# level_shift_panel.net
KiCad netlist of a schematic drawn in EAGLE
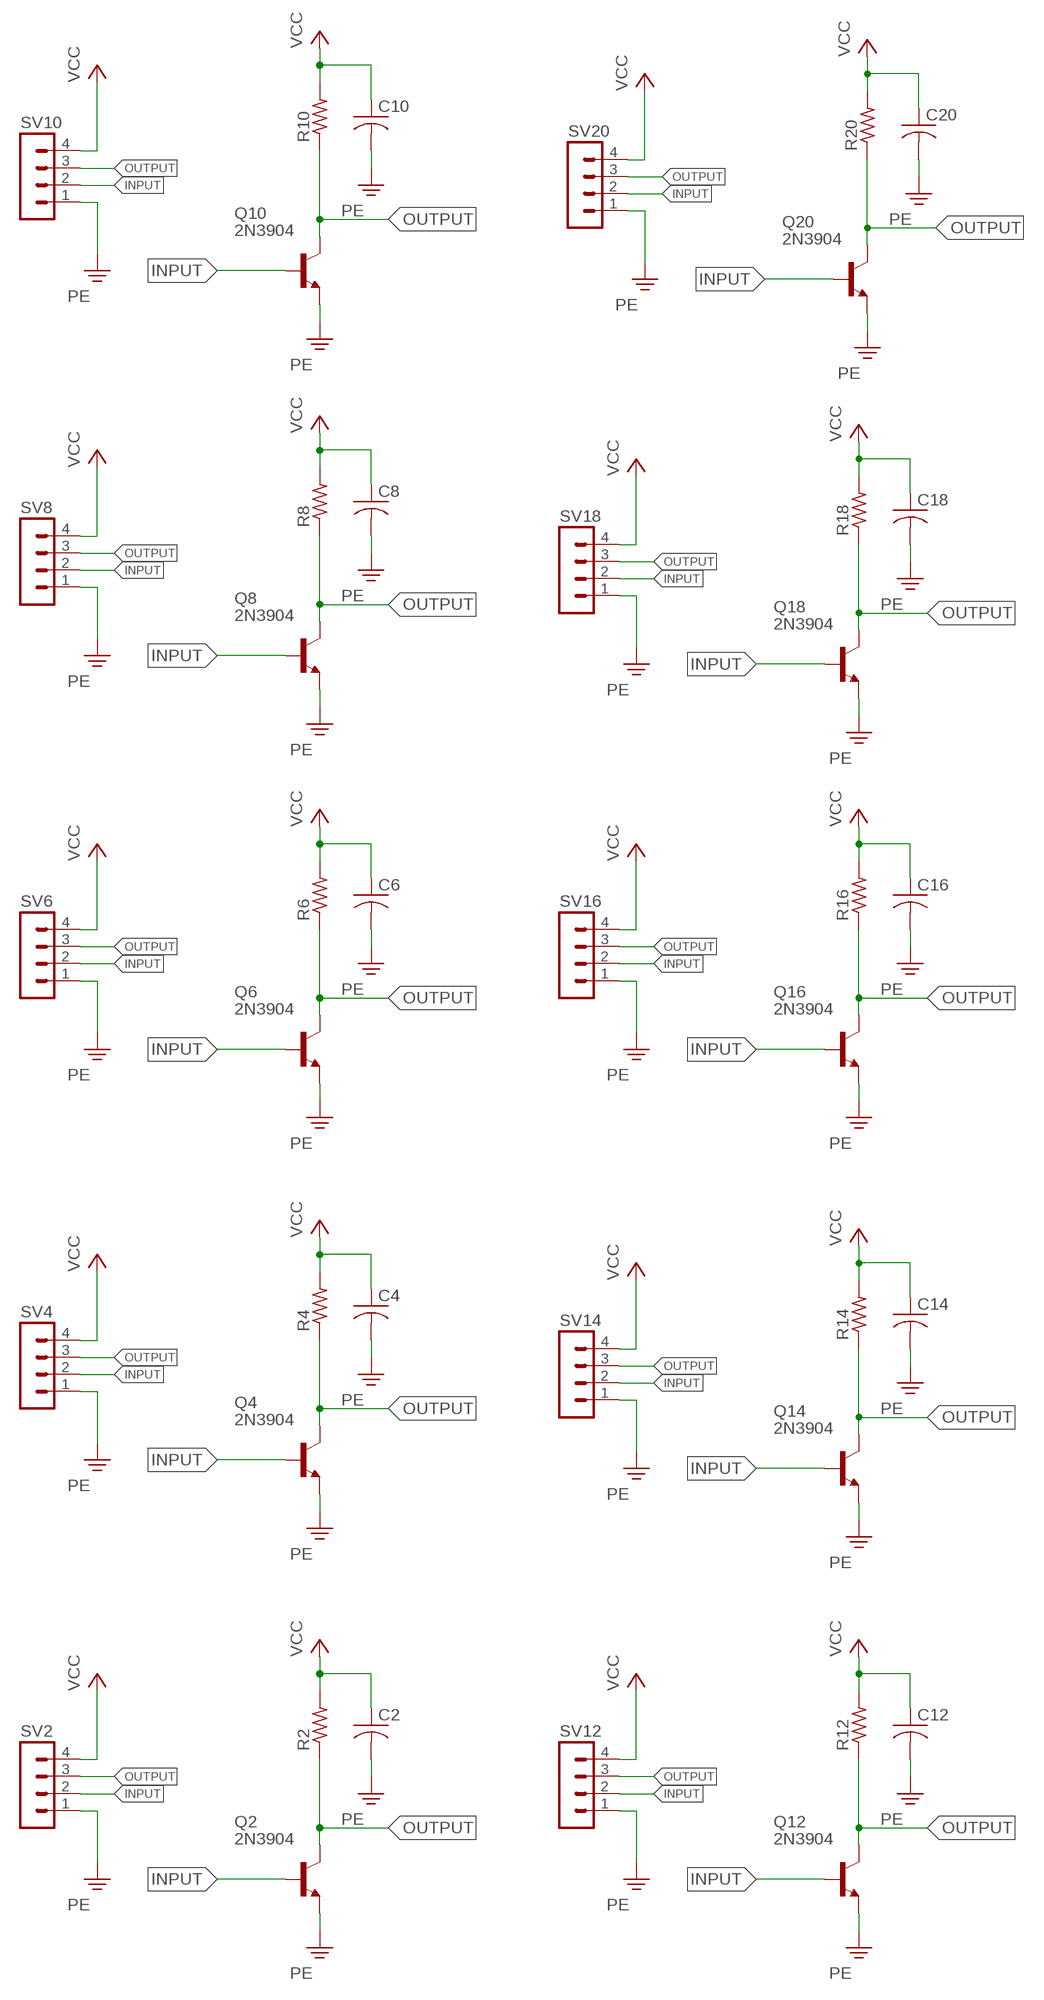
[diagram p0: schematic, sheet 1]

(export (version "E")
  (design (tool "Eeschema 10.0.6"))
  (components
    (comp (ref "C2")
      (value "C-US025-030X050")
      (footprint "eagle-import:C025-030X050")
      (libsource (lib "eagle-import") (part "C-US025-030X050"))
    )
    (comp (ref "C4")
      (value "C-US025-030X050")
      (footprint "eagle-import:C025-030X050")
      (libsource (lib "eagle-import") (part "C-US025-030X050"))
    )
    (comp (ref "C6")
      (value "C-US025-030X050")
      (footprint "eagle-import:C025-030X050")
      (libsource (lib "eagle-import") (part "C-US025-030X050"))
    )
    (comp (ref "C8")
      (value "C-US025-030X050")
      (footprint "eagle-import:C025-030X050")
      (libsource (lib "eagle-import") (part "C-US025-030X050"))
    )
    (comp (ref "C10")
      (value "C-US025-030X050")
      (footprint "eagle-import:C025-030X050")
      (libsource (lib "eagle-import") (part "C-US025-030X050"))
    )
    (comp (ref "C12")
      (value "C-US025-030X050")
      (footprint "eagle-import:C025-030X050")
      (libsource (lib "eagle-import") (part "C-US025-030X050"))
    )
    (comp (ref "C14")
      (value "C-US025-030X050")
      (footprint "eagle-import:C025-030X050")
      (libsource (lib "eagle-import") (part "C-US025-030X050"))
    )
    (comp (ref "C16")
      (value "C-US025-030X050")
      (footprint "eagle-import:C025-030X050")
      (libsource (lib "eagle-import") (part "C-US025-030X050"))
    )
    (comp (ref "C18")
      (value "C-US025-030X050")
      (footprint "eagle-import:C025-030X050")
      (libsource (lib "eagle-import") (part "C-US025-030X050"))
    )
    (comp (ref "C20")
      (value "C-US025-030X050")
      (footprint "eagle-import:C025-030X050")
      (libsource (lib "eagle-import") (part "C-US025-030X050"))
    )
    (comp (ref "Q2")
      (value "2N3904")
      (footprint "eagle-import:TO-92")
      (libsource (lib "eagle-import") (part "2N3904"))
    )
    (comp (ref "Q4")
      (value "2N3904")
      (footprint "eagle-import:TO-92")
      (libsource (lib "eagle-import") (part "2N3904"))
    )
    (comp (ref "Q6")
      (value "2N3904")
      (footprint "eagle-import:TO-92")
      (libsource (lib "eagle-import") (part "2N3904"))
    )
    (comp (ref "Q8")
      (value "2N3904")
      (footprint "eagle-import:TO-92")
      (libsource (lib "eagle-import") (part "2N3904"))
    )
    (comp (ref "Q10")
      (value "2N3904")
      (footprint "eagle-import:TO-92")
      (libsource (lib "eagle-import") (part "2N3904"))
    )
    (comp (ref "Q12")
      (value "2N3904")
      (footprint "eagle-import:TO-92")
      (libsource (lib "eagle-import") (part "2N3904"))
    )
    (comp (ref "Q14")
      (value "2N3904")
      (footprint "eagle-import:TO-92")
      (libsource (lib "eagle-import") (part "2N3904"))
    )
    (comp (ref "Q16")
      (value "2N3904")
      (footprint "eagle-import:TO-92")
      (libsource (lib "eagle-import") (part "2N3904"))
    )
    (comp (ref "Q18")
      (value "2N3904")
      (footprint "eagle-import:TO-92")
      (libsource (lib "eagle-import") (part "2N3904"))
    )
    (comp (ref "Q20")
      (value "2N3904")
      (footprint "eagle-import:TO-92")
      (libsource (lib "eagle-import") (part "2N3904"))
    )
    (comp (ref "R2")
      (value "R-US_0204/7")
      (footprint "eagle-import:0204_7")
      (libsource (lib "eagle-import") (part "R-US_0204/7"))
    )
    (comp (ref "R4")
      (value "R-US_0204/7")
      (footprint "eagle-import:0204_7")
      (libsource (lib "eagle-import") (part "R-US_0204/7"))
    )
    (comp (ref "R6")
      (value "R-US_0204/7")
      (footprint "eagle-import:0204_7")
      (libsource (lib "eagle-import") (part "R-US_0204/7"))
    )
    (comp (ref "R8")
      (value "R-US_0204/7")
      (footprint "eagle-import:0204_7")
      (libsource (lib "eagle-import") (part "R-US_0204/7"))
    )
    (comp (ref "R10")
      (value "R-US_0204/7")
      (footprint "eagle-import:0204_7")
      (libsource (lib "eagle-import") (part "R-US_0204/7"))
    )
    (comp (ref "R12")
      (value "R-US_0204/7")
      (footprint "eagle-import:0204_7")
      (libsource (lib "eagle-import") (part "R-US_0204/7"))
    )
    (comp (ref "R14")
      (value "R-US_0204/7")
      (footprint "eagle-import:0204_7")
      (libsource (lib "eagle-import") (part "R-US_0204/7"))
    )
    (comp (ref "R16")
      (value "R-US_0204/7")
      (footprint "eagle-import:0204_7")
      (libsource (lib "eagle-import") (part "R-US_0204/7"))
    )
    (comp (ref "R18")
      (value "R-US_0204/7")
      (footprint "eagle-import:0204_7")
      (libsource (lib "eagle-import") (part "R-US_0204/7"))
    )
    (comp (ref "R20")
      (value "R-US_0204/7")
      (footprint "eagle-import:0204_7")
      (libsource (lib "eagle-import") (part "R-US_0204/7"))
    )
    (comp (ref "SV2")
      (value "MA04-1")
      (footprint "eagle-import:MA04-1")
      (libsource (lib "eagle-import") (part "MA04-1"))
    )
    (comp (ref "SV4")
      (value "MA04-1")
      (footprint "eagle-import:MA04-1")
      (libsource (lib "eagle-import") (part "MA04-1"))
    )
    (comp (ref "SV6")
      (value "MA04-1")
      (footprint "eagle-import:MA04-1")
      (libsource (lib "eagle-import") (part "MA04-1"))
    )
    (comp (ref "SV8")
      (value "MA04-1")
      (footprint "eagle-import:MA04-1")
      (libsource (lib "eagle-import") (part "MA04-1"))
    )
    (comp (ref "SV10")
      (value "MA04-1")
      (footprint "eagle-import:MA04-1")
      (libsource (lib "eagle-import") (part "MA04-1"))
    )
    (comp (ref "SV12")
      (value "MA04-1")
      (footprint "eagle-import:MA04-1")
      (libsource (lib "eagle-import") (part "MA04-1"))
    )
    (comp (ref "SV14")
      (value "MA04-1")
      (footprint "eagle-import:MA04-1")
      (libsource (lib "eagle-import") (part "MA04-1"))
    )
    (comp (ref "SV16")
      (value "MA04-1")
      (footprint "eagle-import:MA04-1")
      (libsource (lib "eagle-import") (part "MA04-1"))
    )
    (comp (ref "SV18")
      (value "MA04-1")
      (footprint "eagle-import:MA04-1")
      (libsource (lib "eagle-import") (part "MA04-1"))
    )
    (comp (ref "SV20")
      (value "MA04-1")
      (footprint "eagle-import:MA04-1")
      (libsource (lib "eagle-import") (part "MA04-1"))
    )
  )
  (nets
    (net (code "1") (name "INPUT") (class "Default")
      (node (ref "Q10") (pin "B") (pinfunction "B_B") (pintype "passive"))
      (node (ref "Q12") (pin "B") (pinfunction "B_B") (pintype "passive"))
      (node (ref "Q14") (pin "B") (pinfunction "B_B") (pintype "passive"))
      (node (ref "Q16") (pin "B") (pinfunction "B_B") (pintype "passive"))
      (node (ref "Q18") (pin "B") (pinfunction "B_B") (pintype "passive"))
      (node (ref "Q2") (pin "B") (pinfunction "B_B") (pintype "passive"))
      (node (ref "Q20") (pin "B") (pinfunction "B_B") (pintype "passive"))
      (node (ref "Q4") (pin "B") (pinfunction "B_B") (pintype "passive"))
      (node (ref "Q6") (pin "B") (pinfunction "B_B") (pintype "passive"))
      (node (ref "Q8") (pin "B") (pinfunction "B_B") (pintype "passive"))
      (node (ref "SV10") (pin "2") (pinfunction "2_2") (pintype "passive"))
      (node (ref "SV12") (pin "2") (pinfunction "2_2") (pintype "passive"))
      (node (ref "SV14") (pin "2") (pinfunction "2_2") (pintype "passive"))
      (node (ref "SV16") (pin "2") (pinfunction "2_2") (pintype "passive"))
      (node (ref "SV18") (pin "2") (pinfunction "2_2") (pintype "passive"))
      (node (ref "SV2") (pin "2") (pinfunction "2_2") (pintype "passive"))
      (node (ref "SV20") (pin "2") (pinfunction "2_2") (pintype "passive"))
      (node (ref "SV4") (pin "2") (pinfunction "2_2") (pintype "passive"))
      (node (ref "SV6") (pin "2") (pinfunction "2_2") (pintype "passive"))
      (node (ref "SV8") (pin "2") (pinfunction "2_2") (pintype "passive"))
    )
    (net (code "2") (name "OUTPUT") (class "Default")
      (node (ref "Q10") (pin "C") (pinfunction "C_C") (pintype "passive"))
      (node (ref "Q12") (pin "C") (pinfunction "C_C") (pintype "passive"))
      (node (ref "Q14") (pin "C") (pinfunction "C_C") (pintype "passive"))
      (node (ref "Q16") (pin "C") (pinfunction "C_C") (pintype "passive"))
      (node (ref "Q18") (pin "C") (pinfunction "C_C") (pintype "passive"))
      (node (ref "Q2") (pin "C") (pinfunction "C_C") (pintype "passive"))
      (node (ref "Q20") (pin "C") (pinfunction "C_C") (pintype "passive"))
      (node (ref "Q4") (pin "C") (pinfunction "C_C") (pintype "passive"))
      (node (ref "Q6") (pin "C") (pinfunction "C_C") (pintype "passive"))
      (node (ref "Q8") (pin "C") (pinfunction "C_C") (pintype "passive"))
      (node (ref "R10") (pin "1") (pinfunction "1_1") (pintype "passive"))
      (node (ref "R12") (pin "1") (pinfunction "1_1") (pintype "passive"))
      (node (ref "R14") (pin "1") (pinfunction "1_1") (pintype "passive"))
      (node (ref "R16") (pin "1") (pinfunction "1_1") (pintype "passive"))
      (node (ref "R18") (pin "1") (pinfunction "1_1") (pintype "passive"))
      (node (ref "R2") (pin "1") (pinfunction "1_1") (pintype "passive"))
      (node (ref "R20") (pin "1") (pinfunction "1_1") (pintype "passive"))
      (node (ref "R4") (pin "1") (pinfunction "1_1") (pintype "passive"))
      (node (ref "R6") (pin "1") (pinfunction "1_1") (pintype "passive"))
      (node (ref "R8") (pin "1") (pinfunction "1_1") (pintype "passive"))
      (node (ref "SV10") (pin "3") (pinfunction "3_3") (pintype "passive"))
      (node (ref "SV12") (pin "3") (pinfunction "3_3") (pintype "passive"))
      (node (ref "SV14") (pin "3") (pinfunction "3_3") (pintype "passive"))
      (node (ref "SV16") (pin "3") (pinfunction "3_3") (pintype "passive"))
      (node (ref "SV18") (pin "3") (pinfunction "3_3") (pintype "passive"))
      (node (ref "SV2") (pin "3") (pinfunction "3_3") (pintype "passive"))
      (node (ref "SV20") (pin "3") (pinfunction "3_3") (pintype "passive"))
      (node (ref "SV4") (pin "3") (pinfunction "3_3") (pintype "passive"))
      (node (ref "SV6") (pin "3") (pinfunction "3_3") (pintype "passive"))
      (node (ref "SV8") (pin "3") (pinfunction "3_3") (pintype "passive"))
    )
    (net (code "3") (name "PE") (class "Default")
      (node (ref "C10") (pin "2") (pinfunction "2_2") (pintype "passive"))
      (node (ref "C12") (pin "2") (pinfunction "2_2") (pintype "passive"))
      (node (ref "C14") (pin "2") (pinfunction "2_2") (pintype "passive"))
      (node (ref "C16") (pin "2") (pinfunction "2_2") (pintype "passive"))
      (node (ref "C18") (pin "2") (pinfunction "2_2") (pintype "passive"))
      (node (ref "C2") (pin "2") (pinfunction "2_2") (pintype "passive"))
      (node (ref "C20") (pin "2") (pinfunction "2_2") (pintype "passive"))
      (node (ref "C4") (pin "2") (pinfunction "2_2") (pintype "passive"))
      (node (ref "C6") (pin "2") (pinfunction "2_2") (pintype "passive"))
      (node (ref "C8") (pin "2") (pinfunction "2_2") (pintype "passive"))
      (node (ref "Q10") (pin "E") (pinfunction "E_E") (pintype "passive"))
      (node (ref "Q12") (pin "E") (pinfunction "E_E") (pintype "passive"))
      (node (ref "Q14") (pin "E") (pinfunction "E_E") (pintype "passive"))
      (node (ref "Q16") (pin "E") (pinfunction "E_E") (pintype "passive"))
      (node (ref "Q18") (pin "E") (pinfunction "E_E") (pintype "passive"))
      (node (ref "Q2") (pin "E") (pinfunction "E_E") (pintype "passive"))
      (node (ref "Q20") (pin "E") (pinfunction "E_E") (pintype "passive"))
      (node (ref "Q4") (pin "E") (pinfunction "E_E") (pintype "passive"))
      (node (ref "Q6") (pin "E") (pinfunction "E_E") (pintype "passive"))
      (node (ref "Q8") (pin "E") (pinfunction "E_E") (pintype "passive"))
      (node (ref "SV10") (pin "1") (pinfunction "1_1") (pintype "passive"))
      (node (ref "SV12") (pin "1") (pinfunction "1_1") (pintype "passive"))
      (node (ref "SV14") (pin "1") (pinfunction "1_1") (pintype "passive"))
      (node (ref "SV16") (pin "1") (pinfunction "1_1") (pintype "passive"))
      (node (ref "SV18") (pin "1") (pinfunction "1_1") (pintype "passive"))
      (node (ref "SV2") (pin "1") (pinfunction "1_1") (pintype "passive"))
      (node (ref "SV20") (pin "1") (pinfunction "1_1") (pintype "passive"))
      (node (ref "SV4") (pin "1") (pinfunction "1_1") (pintype "passive"))
      (node (ref "SV6") (pin "1") (pinfunction "1_1") (pintype "passive"))
      (node (ref "SV8") (pin "1") (pinfunction "1_1") (pintype "passive"))
    )
    (net (code "4") (name "VCC") (class "Default")
      (node (ref "C10") (pin "1") (pinfunction "1_1") (pintype "passive"))
      (node (ref "C12") (pin "1") (pinfunction "1_1") (pintype "passive"))
      (node (ref "C14") (pin "1") (pinfunction "1_1") (pintype "passive"))
      (node (ref "C16") (pin "1") (pinfunction "1_1") (pintype "passive"))
      (node (ref "C18") (pin "1") (pinfunction "1_1") (pintype "passive"))
      (node (ref "C2") (pin "1") (pinfunction "1_1") (pintype "passive"))
      (node (ref "C20") (pin "1") (pinfunction "1_1") (pintype "passive"))
      (node (ref "C4") (pin "1") (pinfunction "1_1") (pintype "passive"))
      (node (ref "C6") (pin "1") (pinfunction "1_1") (pintype "passive"))
      (node (ref "C8") (pin "1") (pinfunction "1_1") (pintype "passive"))
      (node (ref "R10") (pin "2") (pinfunction "2_2") (pintype "passive"))
      (node (ref "R12") (pin "2") (pinfunction "2_2") (pintype "passive"))
      (node (ref "R14") (pin "2") (pinfunction "2_2") (pintype "passive"))
      (node (ref "R16") (pin "2") (pinfunction "2_2") (pintype "passive"))
      (node (ref "R18") (pin "2") (pinfunction "2_2") (pintype "passive"))
      (node (ref "R2") (pin "2") (pinfunction "2_2") (pintype "passive"))
      (node (ref "R20") (pin "2") (pinfunction "2_2") (pintype "passive"))
      (node (ref "R4") (pin "2") (pinfunction "2_2") (pintype "passive"))
      (node (ref "R6") (pin "2") (pinfunction "2_2") (pintype "passive"))
      (node (ref "R8") (pin "2") (pinfunction "2_2") (pintype "passive"))
      (node (ref "SV10") (pin "4") (pinfunction "4_4") (pintype "passive"))
      (node (ref "SV12") (pin "4") (pinfunction "4_4") (pintype "passive"))
      (node (ref "SV14") (pin "4") (pinfunction "4_4") (pintype "passive"))
      (node (ref "SV16") (pin "4") (pinfunction "4_4") (pintype "passive"))
      (node (ref "SV18") (pin "4") (pinfunction "4_4") (pintype "passive"))
      (node (ref "SV2") (pin "4") (pinfunction "4_4") (pintype "passive"))
      (node (ref "SV20") (pin "4") (pinfunction "4_4") (pintype "passive"))
      (node (ref "SV4") (pin "4") (pinfunction "4_4") (pintype "passive"))
      (node (ref "SV6") (pin "4") (pinfunction "4_4") (pintype "passive"))
      (node (ref "SV8") (pin "4") (pinfunction "4_4") (pintype "passive"))
    )
  )
)
